# controle_com_2dimmer_powerjack.net
KiCad netlist of a schematic drawn in EAGLE
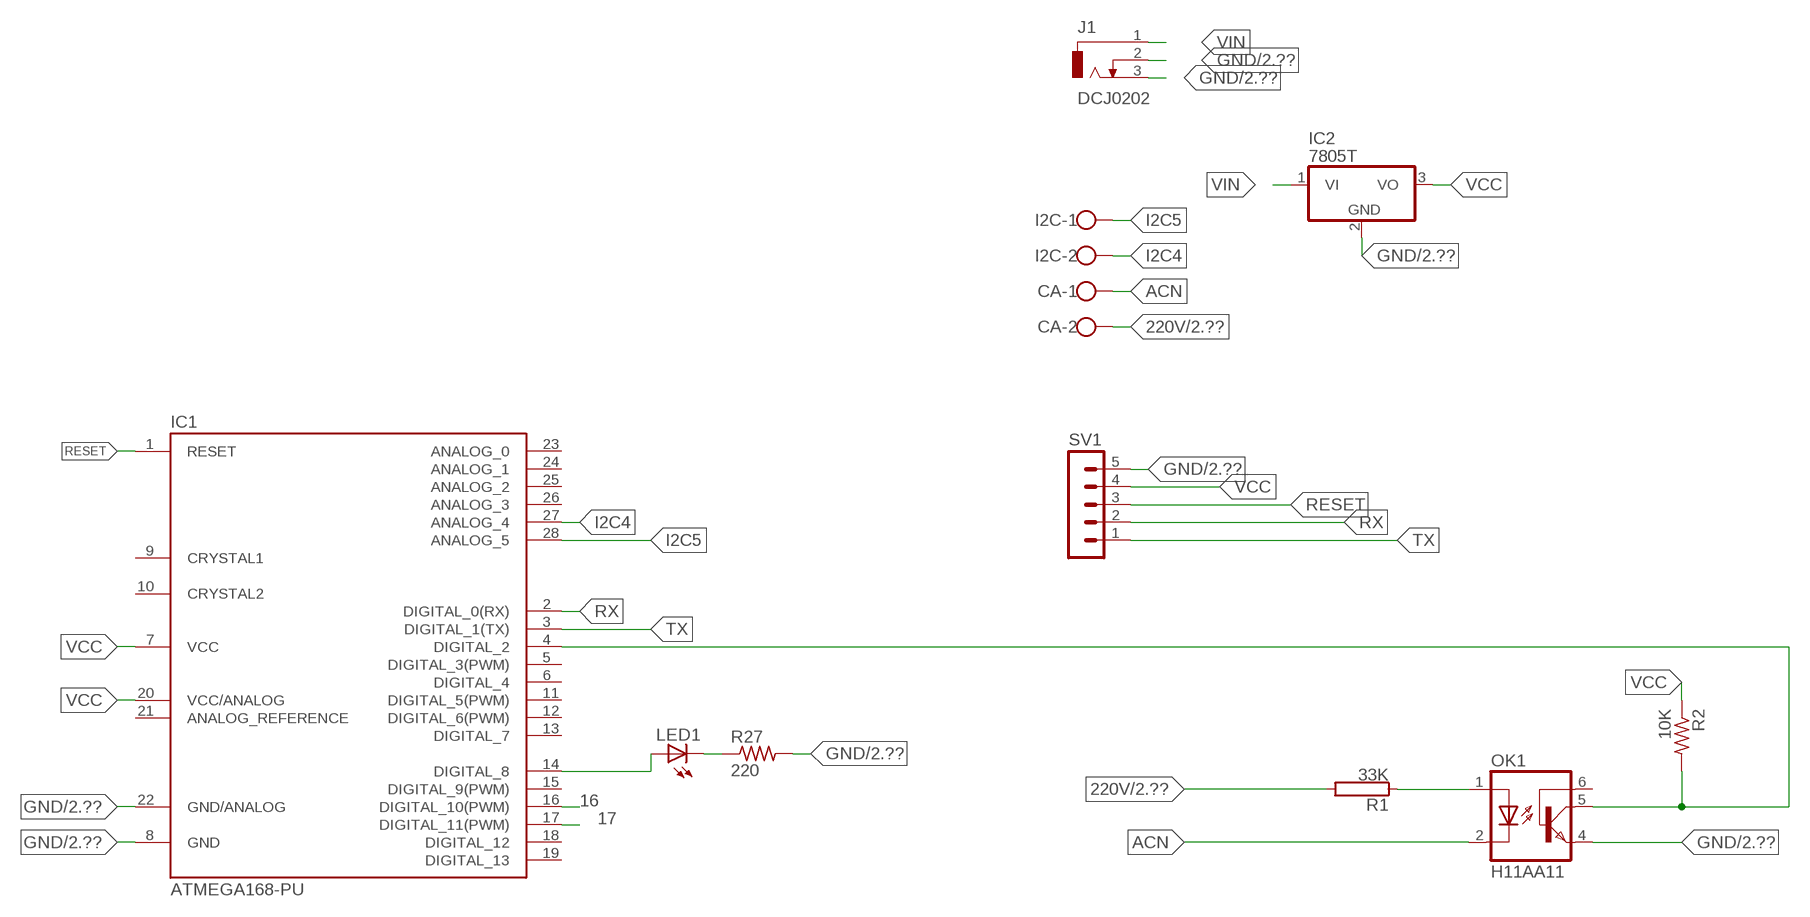
[diagram p0: schematic, sheet 1]
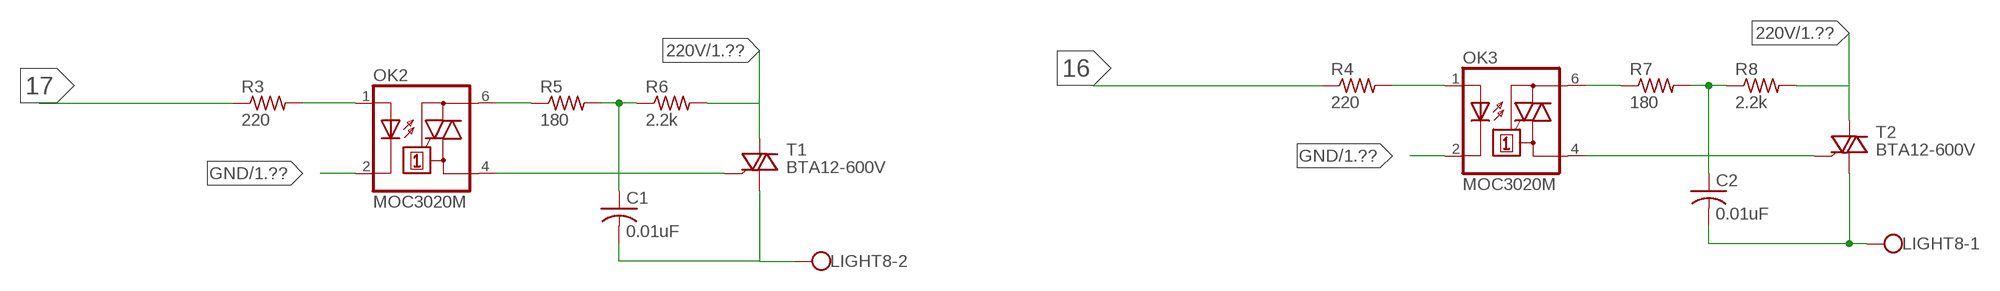
[diagram p1: schematic, sheet 2]

(export (version "E")
  (design (tool "Eeschema 10.0.6"))
  (components
    (comp (ref "C1")
      (value "0.01uF")
      (footprint "eagle-import:C075-042X103")
      (libsource (lib "eagle-import") (part "C-US075-042X103"))
    )
    (comp (ref "C2")
      (value "0.01uF")
      (footprint "eagle-import:C075-042X103")
      (libsource (lib "eagle-import") (part "C-US075-042X103"))
    )
    (comp (ref "LIGHT8")
      (value "W237-102")
      (footprint "eagle-import:W237-102")
      (fields (field (name "MPN") "237-102"))
      (libsource (lib "eagle-import") (part "W237-102"))
    )
    (comp (ref "OK2")
      (value "MOC3020M")
      (footprint "eagle-import:DIL06")
      (fields (field (name "MF") "FAIRCHILD SEMICONDUCTOR") (field (name "MPN") "MOC3020-M"))
      (libsource (lib "eagle-import") (part "MOC30M20"))
    )
    (comp (ref "OK3")
      (value "MOC3020M")
      (footprint "eagle-import:DIL06")
      (fields (field (name "MF") "FAIRCHILD SEMICONDUCTOR") (field (name "MPN") "MOC3020-M"))
      (libsource (lib "eagle-import") (part "MOC30M20"))
    )
    (comp (ref "R3")
      (value "220")
      (footprint "eagle-import:0207_7")
      (libsource (lib "eagle-import") (part "R-US_0207/7"))
    )
    (comp (ref "R4")
      (value "220")
      (footprint "eagle-import:0207_7")
      (libsource (lib "eagle-import") (part "R-US_0207/7"))
    )
    (comp (ref "R5")
      (value "180")
      (footprint "eagle-import:0309_10")
      (libsource (lib "eagle-import") (part "R-US_0309/10"))
    )
    (comp (ref "R6")
      (value "2.2k")
      (footprint "eagle-import:0309_10")
      (libsource (lib "eagle-import") (part "R-US_0309/10"))
    )
    (comp (ref "R7")
      (value "180")
      (footprint "eagle-import:0309_10")
      (libsource (lib "eagle-import") (part "R-US_0309/10"))
    )
    (comp (ref "R8")
      (value "2.2k")
      (footprint "eagle-import:0309_10")
      (libsource (lib "eagle-import") (part "R-US_0309/10"))
    )
    (comp (ref "T1")
      (value "BTA12-600V")
      (footprint "eagle-import:TO220V")
      (libsource (lib "eagle-import") (part "BTA12-600V"))
    )
    (comp (ref "T2")
      (value "BTA12-600V")
      (footprint "eagle-import:TO220V")
      (libsource (lib "eagle-import") (part "BTA12-600V"))
    )
    (comp (ref "CA")
      (value "W237-102")
      (footprint "eagle-import:W237-102")
      (fields (field (name "MPN") "237-102"))
      (libsource (lib "eagle-import") (part "W237-102"))
    )
    (comp (ref "I2C")
      (value "W237-102")
      (footprint "eagle-import:W237-102")
      (fields (field (name "MPN") "237-102"))
      (libsource (lib "eagle-import") (part "W237-102"))
    )
    (comp (ref "IC1")
      (value "ATMEGA168-PU")
      (footprint "eagle-import:DIL28-3")
      (libsource (lib "eagle-import") (part "ATMEGA168-PU"))
    )
    (comp (ref "IC2")
      (value "7805T")
      (footprint "eagle-import:TO220H")
      (libsource (lib "eagle-import") (part "78T05"))
    )
    (comp (ref "J1")
      (value "DCJ0202")
      (footprint "eagle-import:DCJ0202")
      (libsource (lib "eagle-import") (part "DCJ0202"))
    )
    (comp (ref "LED1")
      (value "LED3MM")
      (footprint "eagle-import:LED3MM")
      (libsource (lib "eagle-import") (part "LED3MM"))
    )
    (comp (ref "OK1")
      (value "H11AA11")
      (footprint "eagle-import:DIL06")
      (fields (field (name "MPN") "H11A1-M"))
      (libsource (lib "eagle-import") (part "H11AA11"))
    )
    (comp (ref "R1")
      (value "33K")
      (footprint "eagle-import:KH206-8R")
      (libsource (lib "eagle-import") (part "RKH206-8R"))
    )
    (comp (ref "R2")
      (value "10K")
      (footprint "eagle-import:0207_7")
      (libsource (lib "eagle-import") (part "R-US_0207/7"))
    )
    (comp (ref "R27")
      (value "220")
      (footprint "eagle-import:0207_7")
      (libsource (lib "eagle-import") (part "R-US_0207/7"))
    )
    (comp (ref "SV1")
      (value "MA05-1")
      (footprint "eagle-import:MA05-1")
      (libsource (lib "eagle-import") (part "MA05-1"))
    )
  )
  (nets
    (net (code "1") (name "16") (class "Default")
      (node (ref "IC1") (pin "16") (pinfunction "DIGITAL_10(PWM)_16") (pintype "bidirectional"))
      (node (ref "R4") (pin "1") (pinfunction "1_1") (pintype "passive"))
    )
    (net (code "2") (name "17") (class "Default")
      (node (ref "IC1") (pin "17") (pinfunction "DIGITAL_11(PWM)_17") (pintype "bidirectional"))
      (node (ref "R3") (pin "1") (pinfunction "1_1") (pintype "passive"))
    )
    (net (code "3") (name "220V") (class "Default")
      (node (ref "CA") (pin "2") (pinfunction "KL_2") (pintype "passive"))
      (node (ref "R1") (pin "2") (pinfunction "2_2") (pintype "passive"))
      (node (ref "R6") (pin "2") (pinfunction "2_2") (pintype "passive"))
      (node (ref "R8") (pin "2") (pinfunction "2_2") (pintype "passive"))
      (node (ref "T1") (pin "2") (pinfunction "A2_2") (pintype "passive"))
      (node (ref "T2") (pin "2") (pinfunction "A2_2") (pintype "passive"))
    )
    (net (code "4") (name "ACN") (class "Default")
      (node (ref "CA") (pin "1") (pinfunction "KL_1") (pintype "passive"))
      (node (ref "OK1") (pin "2") (pinfunction "C_2") (pintype "passive"))
    )
    (net (code "5") (name "GND") (class "Default")
      (node (ref "IC1") (pin "22") (pinfunction "GND/ANALOG_22") (pintype "power_in"))
      (node (ref "IC1") (pin "8") (pinfunction "GND_8") (pintype "power_in"))
      (node (ref "IC2") (pin "2") (pinfunction "GND_2") (pintype "passive"))
      (node (ref "J1") (pin "2") (pinfunction "2_2") (pintype "passive"))
      (node (ref "J1") (pin "3") (pinfunction "3_3") (pintype "passive"))
      (node (ref "OK1") (pin "4") (pinfunction "EMI_4") (pintype "passive"))
      (node (ref "OK2") (pin "2") (pinfunction "C_2") (pintype "passive"))
      (node (ref "OK3") (pin "2") (pinfunction "C_2") (pintype "passive"))
      (node (ref "R27") (pin "2") (pinfunction "2_2") (pintype "passive"))
      (node (ref "SV1") (pin "5") (pinfunction "5_5") (pintype "passive"))
    )
    (net (code "6") (name "I2C4") (class "Default")
      (node (ref "I2C") (pin "2") (pinfunction "KL_2") (pintype "passive"))
      (node (ref "IC1") (pin "27") (pinfunction "ANALOG_4_27") (pintype "bidirectional"))
    )
    (net (code "7") (name "I2C5") (class "Default")
      (node (ref "I2C") (pin "1") (pinfunction "KL_1") (pintype "passive"))
      (node (ref "IC1") (pin "28") (pinfunction "ANALOG_5_28") (pintype "bidirectional"))
    )
    (net (code "8") (name "Net-(C1-Pad1)") (class "Default")
      (node (ref "C1") (pin "1") (pinfunction "1_1") (pintype "passive"))
      (node (ref "R5") (pin "2") (pinfunction "2_2") (pintype "passive"))
      (node (ref "R6") (pin "1") (pinfunction "1_1") (pintype "passive"))
    )
    (net (code "9") (name "Net-(C2-Pad1)") (class "Default")
      (node (ref "C2") (pin "1") (pinfunction "1_1") (pintype "passive"))
      (node (ref "R7") (pin "2") (pinfunction "2_2") (pintype "passive"))
      (node (ref "R8") (pin "1") (pinfunction "1_1") (pintype "passive"))
    )
    (net (code "10") (name "Net-(IC1-DIGITAL_2)") (class "Default")
      (node (ref "IC1") (pin "4") (pinfunction "DIGITAL_2_4") (pintype "bidirectional"))
      (node (ref "OK1") (pin "5") (pinfunction "COL_5") (pintype "passive"))
      (node (ref "R2") (pin "2") (pinfunction "2_2") (pintype "passive"))
    )
    (net (code "11") (name "Net-(IC1-DIGITAL_8)") (class "Default")
      (node (ref "IC1") (pin "14") (pinfunction "DIGITAL_8_14") (pintype "bidirectional"))
      (node (ref "LED1") (pin "A") (pinfunction "A_A") (pintype "passive"))
    )
    (net (code "12") (name "Net-(LED1-C)") (class "Default")
      (node (ref "LED1") (pin "K") (pinfunction "C_K") (pintype "passive"))
      (node (ref "R27") (pin "1") (pinfunction "1_1") (pintype "passive"))
    )
    (net (code "13") (name "Net-(LIGHT8A-KL)") (class "Default")
      (node (ref "C2") (pin "2") (pinfunction "2_2") (pintype "passive"))
      (node (ref "LIGHT8") (pin "1") (pinfunction "KL_1") (pintype "passive"))
      (node (ref "T2") (pin "1") (pinfunction "A1_1") (pintype "passive"))
    )
    (net (code "14") (name "Net-(LIGHT8B-KL)") (class "Default")
      (node (ref "C1") (pin "2") (pinfunction "2_2") (pintype "passive"))
      (node (ref "LIGHT8") (pin "2") (pinfunction "KL_2") (pintype "passive"))
      (node (ref "T1") (pin "1") (pinfunction "A1_1") (pintype "passive"))
    )
    (net (code "15") (name "Net-(OK1-A)") (class "Default")
      (node (ref "OK1") (pin "1") (pinfunction "A_1") (pintype "passive"))
      (node (ref "R1") (pin "1") (pinfunction "1_1") (pintype "passive"))
    )
    (net (code "16") (name "Net-(OK2-A)") (class "Default")
      (node (ref "OK2") (pin "1") (pinfunction "A_1") (pintype "passive"))
      (node (ref "R3") (pin "2") (pinfunction "2_2") (pintype "passive"))
    )
    (net (code "17") (name "Net-(OK2-A1)") (class "Default")
      (node (ref "OK2") (pin "4") (pinfunction "A1_4") (pintype "passive"))
      (node (ref "T1") (pin "3") (pinfunction "G_3") (pintype "passive"))
    )
    (net (code "18") (name "Net-(OK2-A2)") (class "Default")
      (node (ref "OK2") (pin "6") (pinfunction "A2_6") (pintype "passive"))
      (node (ref "R5") (pin "1") (pinfunction "1_1") (pintype "passive"))
    )
    (net (code "19") (name "Net-(OK3-A)") (class "Default")
      (node (ref "OK3") (pin "1") (pinfunction "A_1") (pintype "passive"))
      (node (ref "R4") (pin "2") (pinfunction "2_2") (pintype "passive"))
    )
    (net (code "20") (name "Net-(OK3-A1)") (class "Default")
      (node (ref "OK3") (pin "4") (pinfunction "A1_4") (pintype "passive"))
      (node (ref "T2") (pin "3") (pinfunction "G_3") (pintype "passive"))
    )
    (net (code "21") (name "Net-(OK3-A2)") (class "Default")
      (node (ref "OK3") (pin "6") (pinfunction "A2_6") (pintype "passive"))
      (node (ref "R7") (pin "1") (pinfunction "1_1") (pintype "passive"))
    )
    (net (code "22") (name "RESET") (class "Default")
      (node (ref "IC1") (pin "1") (pinfunction "RESET_1") (pintype "bidirectional"))
      (node (ref "SV1") (pin "3") (pinfunction "3_3") (pintype "passive"))
    )
    (net (code "23") (name "RX") (class "Default")
      (node (ref "IC1") (pin "2") (pinfunction "DIGITAL_0(RX)_2") (pintype "bidirectional"))
      (node (ref "SV1") (pin "2") (pinfunction "2_2") (pintype "passive"))
    )
    (net (code "24") (name "TX") (class "Default")
      (node (ref "IC1") (pin "3") (pinfunction "DIGITAL_1(TX)_3") (pintype "bidirectional"))
      (node (ref "SV1") (pin "1") (pinfunction "1_1") (pintype "passive"))
    )
    (net (code "25") (name "VCC") (class "Default")
      (node (ref "IC1") (pin "20") (pinfunction "VCC/ANALOG_20") (pintype "passive"))
      (node (ref "IC1") (pin "7") (pinfunction "VCC_7") (pintype "power_in"))
      (node (ref "IC2") (pin "3") (pinfunction "VO_3") (pintype "passive"))
      (node (ref "R2") (pin "1") (pinfunction "1_1") (pintype "passive"))
      (node (ref "SV1") (pin "4") (pinfunction "4_4") (pintype "passive"))
    )
    (net (code "26") (name "VIN") (class "Default")
      (node (ref "IC2") (pin "1") (pinfunction "VI_1") (pintype "input"))
      (node (ref "J1") (pin "1") (pinfunction "1_1") (pintype "passive"))
    )
    (net (code "27") (name "unconnected-(IC1-ANALOG_0-Pad23)") (class "Default")
      (node (ref "IC1") (pin "23") (pinfunction "ANALOG_0_23") (pintype "bidirectional"))
    )
    (net (code "28") (name "unconnected-(IC1-ANALOG_1-Pad24)") (class "Default")
      (node (ref "IC1") (pin "24") (pinfunction "ANALOG_1_24") (pintype "bidirectional"))
    )
    (net (code "29") (name "unconnected-(IC1-ANALOG_2-Pad25)") (class "Default")
      (node (ref "IC1") (pin "25") (pinfunction "ANALOG_2_25") (pintype "bidirectional"))
    )
    (net (code "30") (name "unconnected-(IC1-ANALOG_3-Pad26)") (class "Default")
      (node (ref "IC1") (pin "26") (pinfunction "ANALOG_3_26") (pintype "bidirectional"))
    )
    (net (code "31") (name "unconnected-(IC1-ANALOG_REFERENCE-Pad21)") (class "Default")
      (node (ref "IC1") (pin "21") (pinfunction "ANALOG_REFERENCE_21") (pintype "passive"))
    )
    (net (code "32") (name "unconnected-(IC1-CRYSTAL1-Pad9)") (class "Default")
      (node (ref "IC1") (pin "9") (pinfunction "CRYSTAL1_9") (pintype "bidirectional"))
    )
    (net (code "33") (name "unconnected-(IC1-CRYSTAL2-Pad10)") (class "Default")
      (node (ref "IC1") (pin "10") (pinfunction "CRYSTAL2_10") (pintype "bidirectional"))
    )
    (net (code "34") (name "unconnected-(IC1-DIGITAL_3(PWM)-Pad5)") (class "Default")
      (node (ref "IC1") (pin "5") (pinfunction "DIGITAL_3(PWM)_5") (pintype "bidirectional"))
    )
    (net (code "35") (name "unconnected-(IC1-DIGITAL_4-Pad6)") (class "Default")
      (node (ref "IC1") (pin "6") (pinfunction "DIGITAL_4_6") (pintype "bidirectional"))
    )
    (net (code "36") (name "unconnected-(IC1-DIGITAL_5(PWM)-Pad11)") (class "Default")
      (node (ref "IC1") (pin "11") (pinfunction "DIGITAL_5(PWM)_11") (pintype "bidirectional"))
    )
    (net (code "37") (name "unconnected-(IC1-DIGITAL_6(PWM)-Pad12)") (class "Default")
      (node (ref "IC1") (pin "12") (pinfunction "DIGITAL_6(PWM)_12") (pintype "bidirectional"))
    )
    (net (code "38") (name "unconnected-(IC1-DIGITAL_7-Pad13)") (class "Default")
      (node (ref "IC1") (pin "13") (pinfunction "DIGITAL_7_13") (pintype "bidirectional"))
    )
    (net (code "39") (name "unconnected-(IC1-DIGITAL_9(PWM)-Pad15)") (class "Default")
      (node (ref "IC1") (pin "15") (pinfunction "DIGITAL_9(PWM)_15") (pintype "bidirectional"))
    )
    (net (code "40") (name "unconnected-(IC1-DIGITAL_12-Pad18)") (class "Default")
      (node (ref "IC1") (pin "18") (pinfunction "DIGITAL_12_18") (pintype "bidirectional"))
    )
    (net (code "41") (name "unconnected-(IC1-DIGITAL_13-Pad19)") (class "Default")
      (node (ref "IC1") (pin "19") (pinfunction "DIGITAL_13_19") (pintype "bidirectional"))
    )
    (net (code "42") (name "unconnected-(OK1-BAS-Pad6)") (class "Default")
      (node (ref "OK1") (pin "6") (pinfunction "BAS_6") (pintype "passive"))
    )
  )
)
